# NTAG_I2C_plus_Class4_Antenna_v1.net
KiCad netlist of a schematic drawn in EAGLE
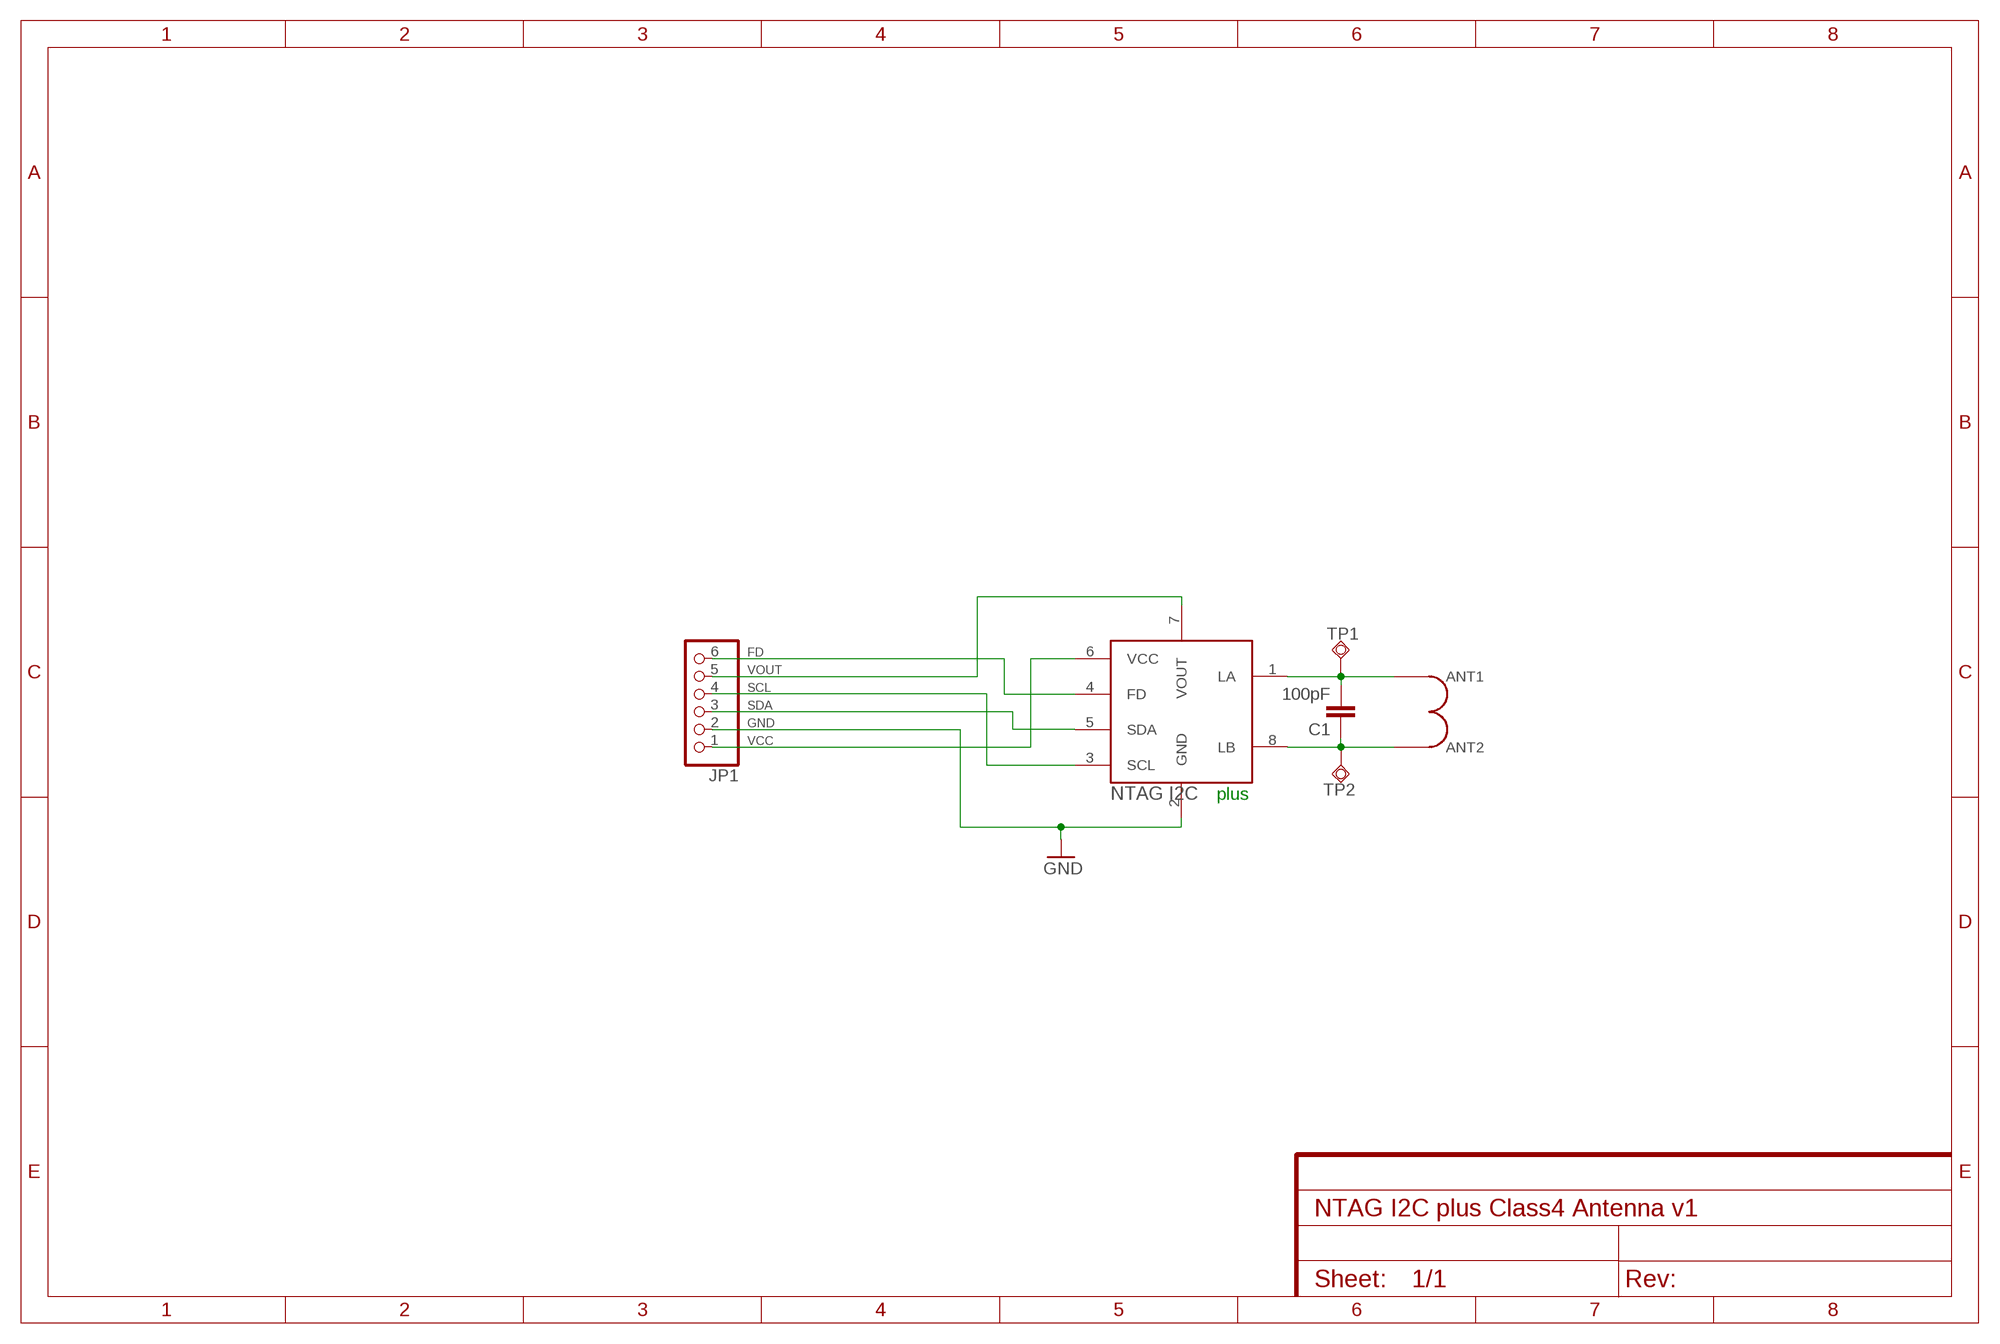
[diagram p0: schematic, sheet 1]

(export (version "E")
  (design (tool "Eeschema 10.0.6"))
  (components
    (comp (ref "C1")
      (value "100pF")
      (footprint "eagle-import:C0402K")
      (libsource (lib "eagle-import") (part "C-EUC0402K"))
    )
    (comp (ref "JP1")
      (value "PINHD-1X6/90")
      (footprint "eagle-import:1X06_90")
      (libsource (lib "eagle-import") (part "PINHD-1X6/90"))
    )
    (comp (ref "TP1")
      (value "TPSQPAD1-13")
      (footprint "eagle-import:P1-13")
      (libsource (lib "eagle-import") (part "TPSQPAD1-13"))
    )
    (comp (ref "TP2")
      (value "TPSQPAD1-13")
      (footprint "eagle-import:P1-13")
      (libsource (lib "eagle-import") (part "TPSQPAD1-13"))
    )
    (comp (ref "U$1")
      (value "ENERGY-HARVESTING_3-TURNS54X27_3TURN_THIN")
      (footprint "eagle-import:54X27_3TURNS_THIN")
      (libsource (lib "eagle-import") (part "ENERGY-HARVESTING_3-TURNS54X27_3TURN_THIN"))
    )
    (comp (ref "U$3")
      (value "NTAG_I2CXQFN8")
      (footprint "eagle-import:SOT902-3")
      (libsource (lib "eagle-import") (part "NTAG_I2CXQFN8"))
    )
  )
  (nets
    (net (code "1") (name "GND") (class "Default")
      (node (ref "JP1") (pin "2") (pinfunction "2_2") (pintype "passive"))
      (node (ref "U$3") (pin "2") (pinfunction "GND_2") (pintype "bidirectional"))
    )
    (net (code "2") (name "Net-(U$3-FD)") (class "Default")
      (node (ref "JP1") (pin "6") (pinfunction "6_6") (pintype "passive"))
      (node (ref "U$3") (pin "4") (pinfunction "FD_4") (pintype "bidirectional"))
    )
    (net (code "3") (name "Net-(U$3-LA)") (class "Default")
      (node (ref "C1") (pin "2") (pinfunction "2_2") (pintype "passive"))
      (node (ref "TP1") (pin "TP") (pinfunction "TP_TP") (pintype "input"))
      (node (ref "U$1") (pin "ANT1") (pinfunction "ANT1_ANT1") (pintype "bidirectional"))
      (node (ref "U$3") (pin "1") (pinfunction "LA_1") (pintype "bidirectional"))
    )
    (net (code "4") (name "Net-(U$3-LB)") (class "Default")
      (node (ref "C1") (pin "1") (pinfunction "1_1") (pintype "passive"))
      (node (ref "TP2") (pin "TP") (pinfunction "TP_TP") (pintype "input"))
      (node (ref "U$1") (pin "ANT2") (pinfunction "ANT2_ANT2") (pintype "bidirectional"))
      (node (ref "U$3") (pin "8") (pinfunction "LB_8") (pintype "bidirectional"))
    )
    (net (code "5") (name "Net-(U$3-SCL)") (class "Default")
      (node (ref "JP1") (pin "4") (pinfunction "4_4") (pintype "passive"))
      (node (ref "U$3") (pin "3") (pinfunction "SCL_3") (pintype "bidirectional"))
    )
    (net (code "6") (name "Net-(U$3-SDA)") (class "Default")
      (node (ref "JP1") (pin "3") (pinfunction "3_3") (pintype "passive"))
      (node (ref "U$3") (pin "5") (pinfunction "SDA_5") (pintype "bidirectional"))
    )
    (net (code "7") (name "Net-(U$3-VCC)") (class "Default")
      (node (ref "JP1") (pin "1") (pinfunction "1_1") (pintype "passive"))
      (node (ref "U$3") (pin "6") (pinfunction "VCC_6") (pintype "bidirectional"))
    )
    (net (code "8") (name "Net-(U$3-VOUT)") (class "Default")
      (node (ref "JP1") (pin "5") (pinfunction "5_5") (pintype "passive"))
      (node (ref "U$3") (pin "7") (pinfunction "VOUT_7") (pintype "bidirectional"))
    )
  )
)
